# SeniorProjectBoard5.net
KiCad netlist of a schematic drawn in EAGLE
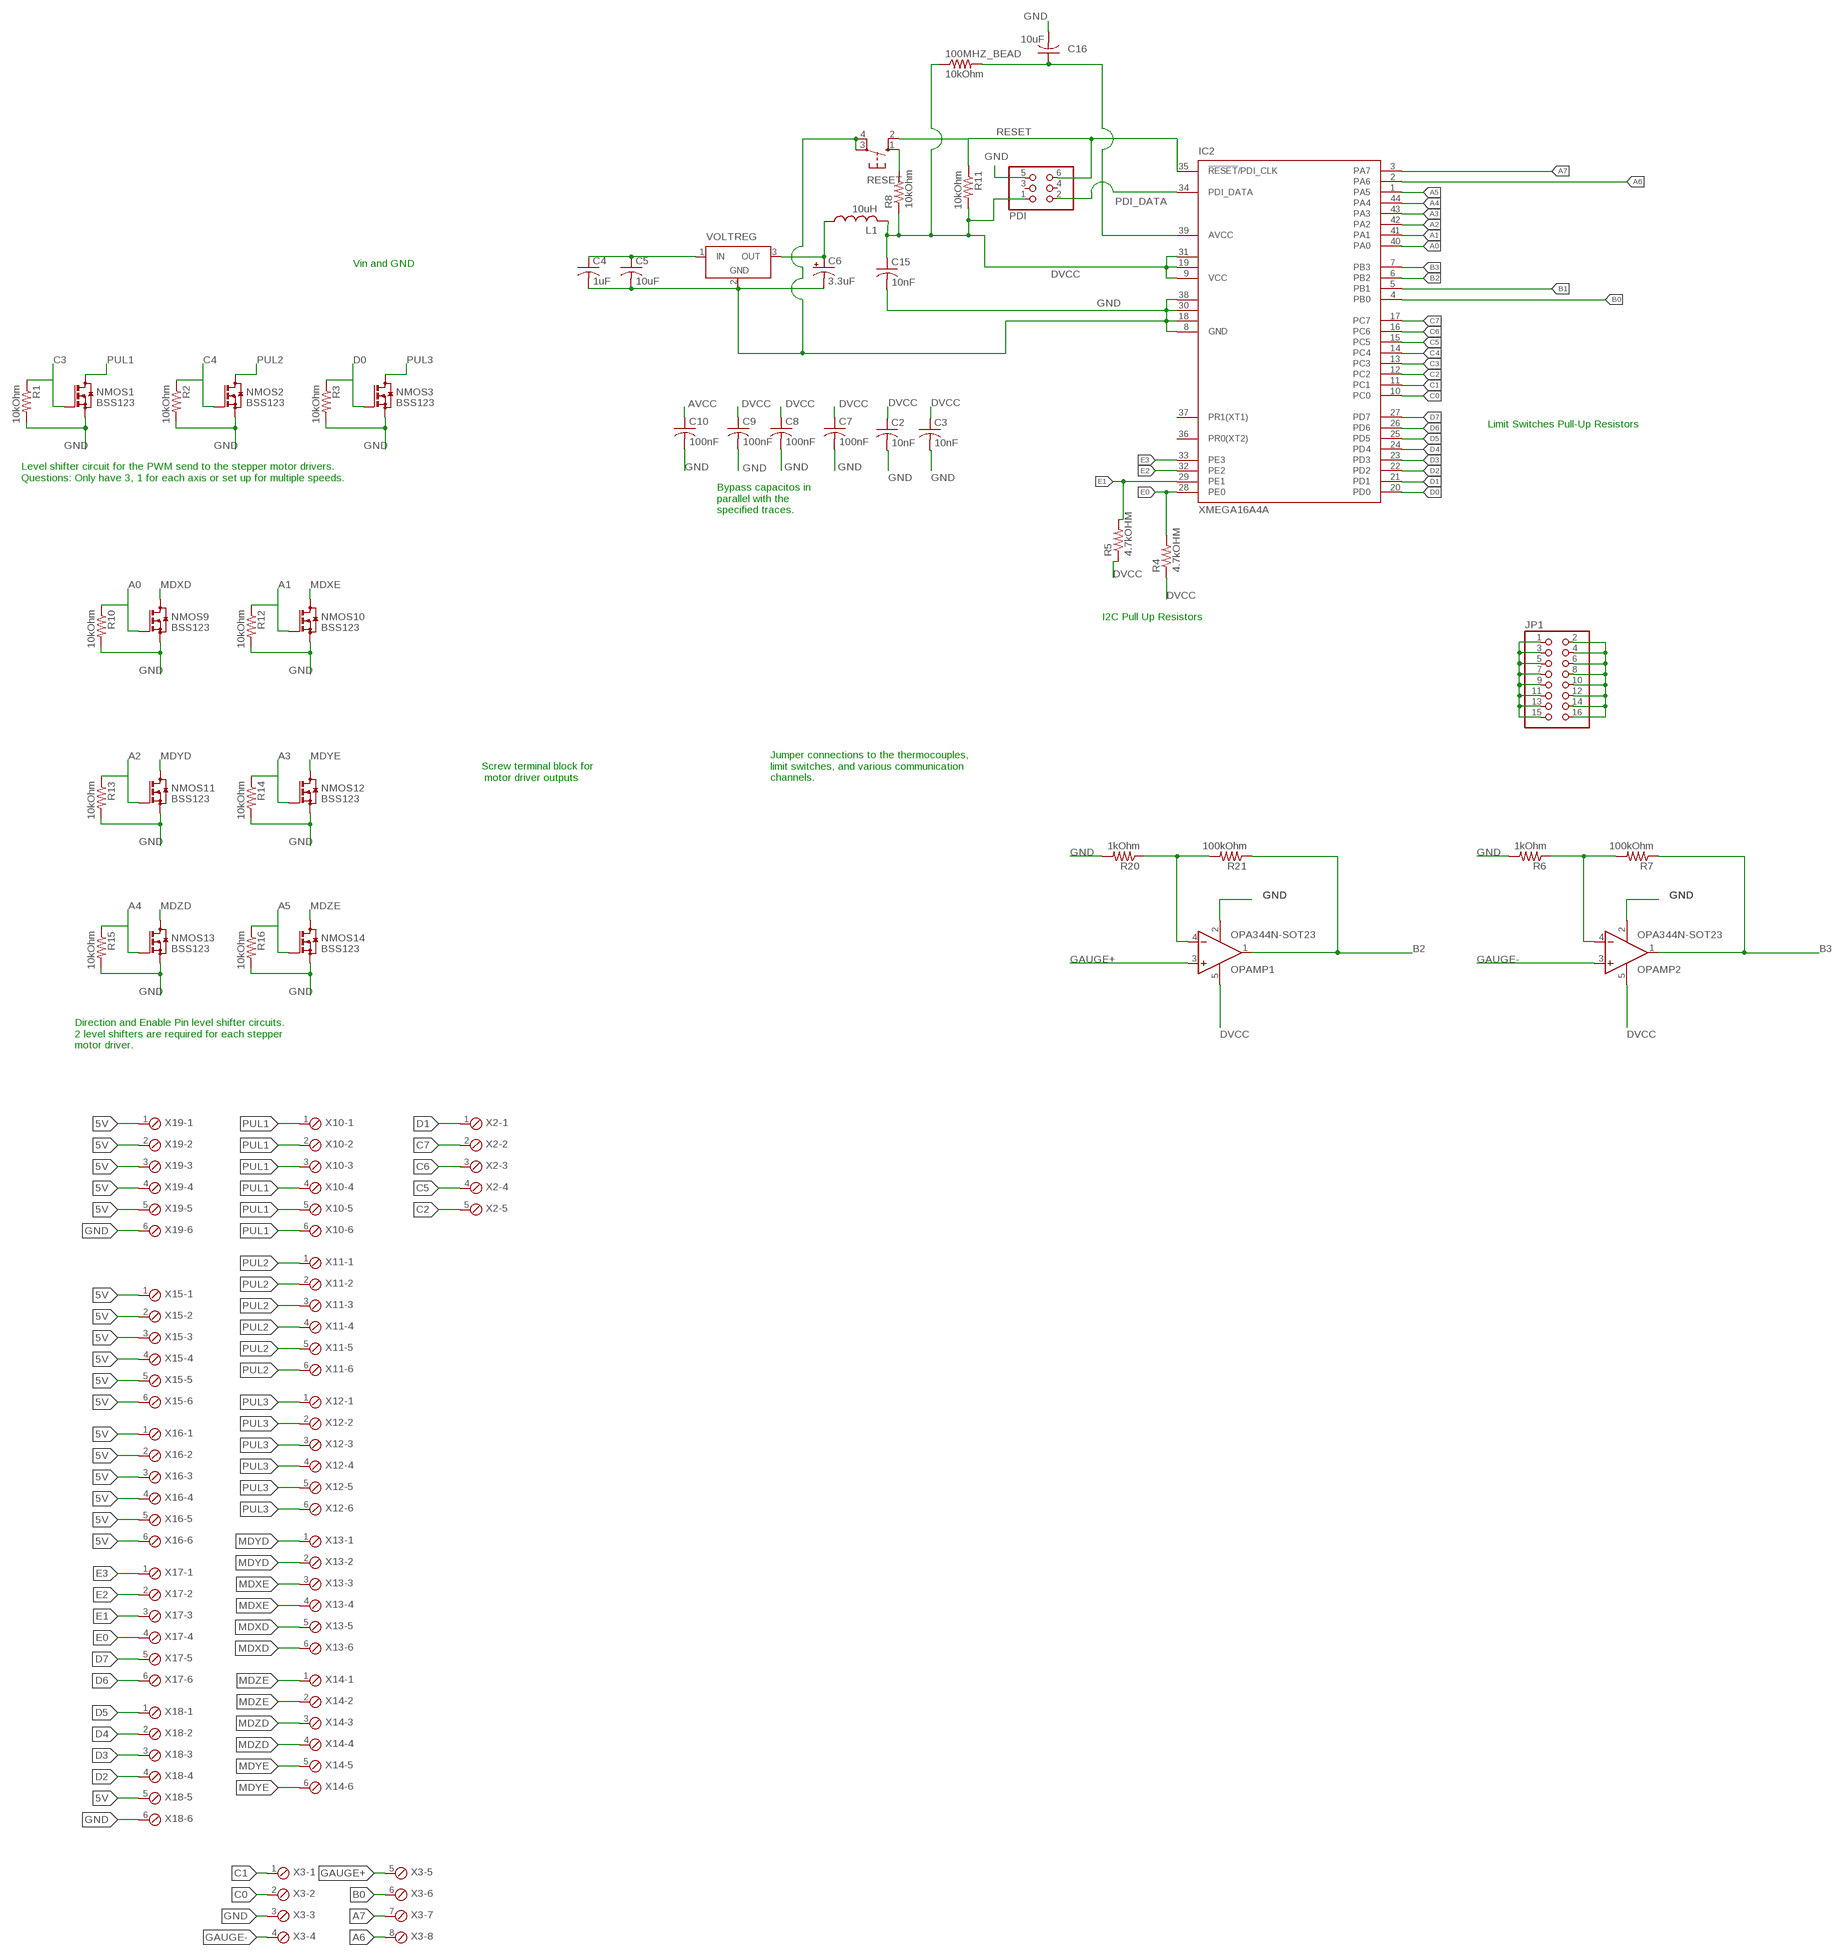
[diagram p0: schematic, sheet 1]

(export (version "E")
  (design (tool "Eeschema 10.0.6"))
  (components
    (comp (ref "100MHZ_BEAD")
      (value "10kOhm")
      (footprint "eagle-import:R0805")
      (libsource (lib "eagle-import") (part "R-US_R0805"))
    )
    (comp (ref "C2")
      (value "10nF")
      (footprint "eagle-import:C0805")
      (libsource (lib "eagle-import") (part "C-USC0805"))
    )
    (comp (ref "C3")
      (value "10nF")
      (footprint "eagle-import:C0805")
      (libsource (lib "eagle-import") (part "C-USC0805"))
    )
    (comp (ref "C4")
      (value "1uF")
      (footprint "eagle-import:C0805")
      (libsource (lib "eagle-import") (part "C-USC0805"))
    )
    (comp (ref "C5")
      (value "10uF")
      (footprint "eagle-import:C0805")
      (libsource (lib "eagle-import") (part "C-USC0805"))
    )
    (comp (ref "C6")
      (value "3.3uF")
      (footprint "eagle-import:CT3216")
      (libsource (lib "eagle-import") (part "CPOL-USCT3216"))
    )
    (comp (ref "C7")
      (value "100nF")
      (footprint "eagle-import:C0805")
      (libsource (lib "eagle-import") (part "C-USC0805"))
    )
    (comp (ref "C8")
      (value "100nF")
      (footprint "eagle-import:C0805")
      (libsource (lib "eagle-import") (part "C-USC0805"))
    )
    (comp (ref "C9")
      (value "100nF")
      (footprint "eagle-import:C0805")
      (libsource (lib "eagle-import") (part "C-USC0805"))
    )
    (comp (ref "C10")
      (value "100nF")
      (footprint "eagle-import:C0805")
      (libsource (lib "eagle-import") (part "C-USC0805"))
    )
    (comp (ref "C15")
      (value "10nF")
      (footprint "eagle-import:C0805")
      (libsource (lib "eagle-import") (part "C-USC0805"))
    )
    (comp (ref "C16")
      (value "10uF")
      (footprint "eagle-import:C0805")
      (libsource (lib "eagle-import") (part "C-USC0805"))
    )
    (comp (ref "IC2")
      (value "XMEGA16A4A")
      (footprint "eagle-import:TQFP44")
      (libsource (lib "eagle-import") (part "XMEGA16A4A"))
    )
    (comp (ref "JP1")
      (value "PINHD-2X8")
      (footprint "eagle-import:2X08")
      (libsource (lib "eagle-import") (part "PINHD-2X8"))
    )
    (comp (ref "L1")
      (value "10uH")
      (footprint "eagle-import:L1812")
      (libsource (lib "eagle-import") (part "L-USL1812"))
    )
    (comp (ref "NMOS1")
      (value "BSS123")
      (footprint "eagle-import:SOT23")
      (libsource (lib "eagle-import") (part "BSS123"))
    )
    (comp (ref "NMOS2")
      (value "BSS123")
      (footprint "eagle-import:SOT23")
      (libsource (lib "eagle-import") (part "BSS123"))
    )
    (comp (ref "NMOS3")
      (value "BSS123")
      (footprint "eagle-import:SOT23")
      (libsource (lib "eagle-import") (part "BSS123"))
    )
    (comp (ref "NMOS9")
      (value "BSS123")
      (footprint "eagle-import:SOT23")
      (libsource (lib "eagle-import") (part "BSS123"))
    )
    (comp (ref "NMOS10")
      (value "BSS123")
      (footprint "eagle-import:SOT23")
      (libsource (lib "eagle-import") (part "BSS123"))
    )
    (comp (ref "NMOS11")
      (value "BSS123")
      (footprint "eagle-import:SOT23")
      (libsource (lib "eagle-import") (part "BSS123"))
    )
    (comp (ref "NMOS12")
      (value "BSS123")
      (footprint "eagle-import:SOT23")
      (libsource (lib "eagle-import") (part "BSS123"))
    )
    (comp (ref "NMOS13")
      (value "BSS123")
      (footprint "eagle-import:SOT23")
      (libsource (lib "eagle-import") (part "BSS123"))
    )
    (comp (ref "NMOS14")
      (value "BSS123")
      (footprint "eagle-import:SOT23")
      (libsource (lib "eagle-import") (part "BSS123"))
    )
    (comp (ref "OPAMP1")
      (value "OPA344N-SOT23")
      (footprint "eagle-import:SOT23-5")
      (libsource (lib "eagle-import") (part "OPA-SOT23344N"))
    )
    (comp (ref "OPAMP2")
      (value "OPA344N-SOT23")
      (footprint "eagle-import:SOT23-5")
      (libsource (lib "eagle-import") (part "OPA-SOT23344N"))
    )
    (comp (ref "PDI")
      (value "PINHD-2X3")
      (footprint "eagle-import:2X03")
      (libsource (lib "eagle-import") (part "PINHD-2X3"))
    )
    (comp (ref "R1")
      (value "10kOhm")
      (footprint "eagle-import:R0805")
      (libsource (lib "eagle-import") (part "R-US_R0805"))
    )
    (comp (ref "R2")
      (value "10kOhm")
      (footprint "eagle-import:R0805")
      (libsource (lib "eagle-import") (part "R-US_R0805"))
    )
    (comp (ref "R3")
      (value "10kOhm")
      (footprint "eagle-import:R0805")
      (libsource (lib "eagle-import") (part "R-US_R0805"))
    )
    (comp (ref "R4")
      (value "4.7kOHM")
      (footprint "eagle-import:R0805")
      (libsource (lib "eagle-import") (part "R-US_R0805"))
    )
    (comp (ref "R5")
      (value "4.7kOHM")
      (footprint "eagle-import:R0805")
      (libsource (lib "eagle-import") (part "R-US_R0805"))
    )
    (comp (ref "R6")
      (value "1kOhm")
      (footprint "eagle-import:R0805")
      (libsource (lib "eagle-import") (part "R-US_R0805"))
    )
    (comp (ref "R7")
      (value "100kOhm")
      (footprint "eagle-import:R0805")
      (libsource (lib "eagle-import") (part "R-US_R0805"))
    )
    (comp (ref "R8")
      (value "10kOhm")
      (footprint "eagle-import:R0805")
      (libsource (lib "eagle-import") (part "R-US_R0805"))
    )
    (comp (ref "R10")
      (value "10kOhm")
      (footprint "eagle-import:R0805")
      (libsource (lib "eagle-import") (part "R-US_R0805"))
    )
    (comp (ref "R11")
      (value "10kOhm")
      (footprint "eagle-import:R0805")
      (libsource (lib "eagle-import") (part "R-US_R0805"))
    )
    (comp (ref "R12")
      (value "10kOhm")
      (footprint "eagle-import:R0805")
      (libsource (lib "eagle-import") (part "R-US_R0805"))
    )
    (comp (ref "R13")
      (value "10kOhm")
      (footprint "eagle-import:R0805")
      (libsource (lib "eagle-import") (part "R-US_R0805"))
    )
    (comp (ref "R14")
      (value "10kOhm")
      (footprint "eagle-import:R0805")
      (libsource (lib "eagle-import") (part "R-US_R0805"))
    )
    (comp (ref "R15")
      (value "10kOhm")
      (footprint "eagle-import:R0805")
      (libsource (lib "eagle-import") (part "R-US_R0805"))
    )
    (comp (ref "R16")
      (value "10kOhm")
      (footprint "eagle-import:R0805")
      (libsource (lib "eagle-import") (part "R-US_R0805"))
    )
    (comp (ref "R20")
      (value "1kOhm")
      (footprint "eagle-import:R0805")
      (libsource (lib "eagle-import") (part "R-US_R0805"))
    )
    (comp (ref "R21")
      (value "100kOhm")
      (footprint "eagle-import:R0805")
      (libsource (lib "eagle-import") (part "R-US_R0805"))
    )
    (comp (ref "RESET")
      (value "10-XX")
      (footprint "eagle-import:B3F-10XX")
      (fields (field (name "MPN") "B3F-1000"))
      (libsource (lib "eagle-import") (part "10-XX"))
    )
    (comp (ref "VOLTREG")
      (value "LT1129CST5")
      (footprint "eagle-import:SOT223")
      (fields (field (name "MPN") "LT1129CST-5#PBF"))
      (libsource (lib "eagle-import") (part "LT1129CST5"))
    )
    (comp (ref "X2")
      (value "MPT5")
      (footprint "eagle-import:5POL254")
      (libsource (lib "eagle-import") (part "MPT5"))
    )
    (comp (ref "X3")
      (value "MPT8")
      (footprint "eagle-import:8POL254")
      (libsource (lib "eagle-import") (part "MPT8"))
    )
    (comp (ref "X10")
      (value "MPT6")
      (footprint "eagle-import:6POL254")
      (libsource (lib "eagle-import") (part "MPT6"))
    )
    (comp (ref "X11")
      (value "MPT6")
      (footprint "eagle-import:6POL254")
      (libsource (lib "eagle-import") (part "MPT6"))
    )
    (comp (ref "X12")
      (value "MPT6")
      (footprint "eagle-import:6POL254")
      (libsource (lib "eagle-import") (part "MPT6"))
    )
    (comp (ref "X13")
      (value "MPT6")
      (footprint "eagle-import:6POL254")
      (libsource (lib "eagle-import") (part "MPT6"))
    )
    (comp (ref "X14")
      (value "MPT6")
      (footprint "eagle-import:6POL254")
      (libsource (lib "eagle-import") (part "MPT6"))
    )
    (comp (ref "X15")
      (value "MPT6")
      (footprint "eagle-import:6POL254")
      (libsource (lib "eagle-import") (part "MPT6"))
    )
    (comp (ref "X16")
      (value "MPT6")
      (footprint "eagle-import:6POL254")
      (libsource (lib "eagle-import") (part "MPT6"))
    )
    (comp (ref "X17")
      (value "MPT6")
      (footprint "eagle-import:6POL254")
      (libsource (lib "eagle-import") (part "MPT6"))
    )
    (comp (ref "X18")
      (value "MPT6")
      (footprint "eagle-import:6POL254")
      (libsource (lib "eagle-import") (part "MPT6"))
    )
    (comp (ref "X19")
      (value "MPT6")
      (footprint "eagle-import:6POL254")
      (libsource (lib "eagle-import") (part "MPT6"))
    )
  )
  (nets
    (net (code "1") (name "/AVCC") (class "Default")
      (node (ref "100MHZ_BEAD") (pin "2") (pinfunction "2_2") (pintype "passive"))
      (node (ref "C10") (pin "1") (pinfunction "1_1") (pintype "passive"))
      (node (ref "C16") (pin "1") (pinfunction "1_1") (pintype "passive"))
      (node (ref "IC2") (pin "39") (pinfunction "AVCC_39") (pintype "power_in"))
    )
    (net (code "2") (name "/DVCC") (class "Default")
      (node (ref "100MHZ_BEAD") (pin "1") (pinfunction "1_1") (pintype "passive"))
      (node (ref "C15") (pin "1") (pinfunction "1_1") (pintype "passive"))
      (node (ref "C2") (pin "1") (pinfunction "1_1") (pintype "passive"))
      (node (ref "C3") (pin "1") (pinfunction "1_1") (pintype "passive"))
      (node (ref "C7") (pin "1") (pinfunction "1_1") (pintype "passive"))
      (node (ref "C8") (pin "1") (pinfunction "1_1") (pintype "passive"))
      (node (ref "C9") (pin "1") (pinfunction "1_1") (pintype "passive"))
      (node (ref "IC2") (pin "19") (pinfunction "VCC1_19") (pintype "power_in"))
      (node (ref "IC2") (pin "31") (pinfunction "VCC2_31") (pintype "power_in"))
      (node (ref "IC2") (pin "9") (pinfunction "VCC_9") (pintype "power_in"))
      (node (ref "JP1") (pin "1") (pinfunction "1_1") (pintype "passive"))
      (node (ref "JP1") (pin "11") (pinfunction "11_11") (pintype "passive"))
      (node (ref "JP1") (pin "13") (pinfunction "13_13") (pintype "passive"))
      (node (ref "JP1") (pin "15") (pinfunction "15_15") (pintype "passive"))
      (node (ref "JP1") (pin "3") (pinfunction "3_3") (pintype "passive"))
      (node (ref "JP1") (pin "5") (pinfunction "5_5") (pintype "passive"))
      (node (ref "JP1") (pin "7") (pinfunction "7_7") (pintype "passive"))
      (node (ref "JP1") (pin "9") (pinfunction "9_9") (pintype "passive"))
      (node (ref "L1") (pin "2") (pinfunction "2_2") (pintype "passive"))
      (node (ref "OPAMP1") (pin "5") (pinfunction "V+_5") (pintype "power_in"))
      (node (ref "OPAMP2") (pin "5") (pinfunction "V+_5") (pintype "power_in"))
      (node (ref "PDI") (pin "1") (pinfunction "1_1") (pintype "passive"))
      (node (ref "R11") (pin "2") (pinfunction "2_2") (pintype "passive"))
      (node (ref "R4") (pin "1") (pinfunction "1_1") (pintype "passive"))
      (node (ref "R5") (pin "1") (pinfunction "1_1") (pintype "passive"))
      (node (ref "R8") (pin "1") (pinfunction "1_1") (pintype "passive"))
    )
    (net (code "3") (name "/PDI_DATA") (class "Default")
      (node (ref "IC2") (pin "34") (pinfunction "PDI_DATA_34") (pintype "bidirectional"))
      (node (ref "PDI") (pin "2") (pinfunction "2_2") (pintype "passive"))
    )
    (net (code "4") (name "/RESET") (class "Default")
      (node (ref "IC2") (pin "35") (pinfunction "~{RESET}/PDI_CLK_35") (pintype "bidirectional"))
      (node (ref "PDI") (pin "6") (pinfunction "6_6") (pintype "passive"))
      (node (ref "R11") (pin "1") (pinfunction "1_1") (pintype "passive"))
      (node (ref "RESET") (pin "2") (pinfunction "S1_2") (pintype "passive"))
    )
    (net (code "5") (name "5V") (class "Default")
      (node (ref "C4") (pin "1") (pinfunction "1_1") (pintype "passive"))
      (node (ref "C5") (pin "1") (pinfunction "1_1") (pintype "passive"))
      (node (ref "VOLTREG") (pin "1") (pinfunction "IN_1") (pintype "input"))
      (node (ref "X15") (pin "1") (pinfunction "1_1") (pintype "passive"))
      (node (ref "X15") (pin "2") (pinfunction "1_2") (pintype "passive"))
      (node (ref "X15") (pin "3") (pinfunction "1_3") (pintype "passive"))
      (node (ref "X15") (pin "4") (pinfunction "1_4") (pintype "passive"))
      (node (ref "X15") (pin "5") (pinfunction "1_5") (pintype "passive"))
      (node (ref "X15") (pin "6") (pinfunction "1_6") (pintype "passive"))
      (node (ref "X16") (pin "1") (pinfunction "1_1") (pintype "passive"))
      (node (ref "X16") (pin "2") (pinfunction "1_2") (pintype "passive"))
      (node (ref "X16") (pin "3") (pinfunction "1_3") (pintype "passive"))
      (node (ref "X16") (pin "4") (pinfunction "1_4") (pintype "passive"))
      (node (ref "X16") (pin "5") (pinfunction "1_5") (pintype "passive"))
      (node (ref "X16") (pin "6") (pinfunction "1_6") (pintype "passive"))
      (node (ref "X18") (pin "5") (pinfunction "1_5") (pintype "passive"))
      (node (ref "X19") (pin "1") (pinfunction "1_1") (pintype "passive"))
      (node (ref "X19") (pin "2") (pinfunction "1_2") (pintype "passive"))
      (node (ref "X19") (pin "3") (pinfunction "1_3") (pintype "passive"))
      (node (ref "X19") (pin "4") (pinfunction "1_4") (pintype "passive"))
      (node (ref "X19") (pin "5") (pinfunction "1_5") (pintype "passive"))
    )
    (net (code "6") (name "A0") (class "Default")
      (node (ref "IC2") (pin "40") (pinfunction "PA0_40") (pintype "bidirectional"))
      (node (ref "NMOS9") (pin "1") (pinfunction "G_1") (pintype "passive"))
      (node (ref "R10") (pin "1") (pinfunction "1_1") (pintype "passive"))
    )
    (net (code "7") (name "A1") (class "Default")
      (node (ref "IC2") (pin "41") (pinfunction "PA1_41") (pintype "bidirectional"))
      (node (ref "NMOS10") (pin "1") (pinfunction "G_1") (pintype "passive"))
      (node (ref "R12") (pin "1") (pinfunction "1_1") (pintype "passive"))
    )
    (net (code "8") (name "A2") (class "Default")
      (node (ref "IC2") (pin "42") (pinfunction "PA2_42") (pintype "bidirectional"))
      (node (ref "NMOS11") (pin "1") (pinfunction "G_1") (pintype "passive"))
      (node (ref "R13") (pin "1") (pinfunction "1_1") (pintype "passive"))
    )
    (net (code "9") (name "A3") (class "Default")
      (node (ref "IC2") (pin "43") (pinfunction "PA3_43") (pintype "bidirectional"))
      (node (ref "NMOS12") (pin "1") (pinfunction "G_1") (pintype "passive"))
      (node (ref "R14") (pin "1") (pinfunction "1_1") (pintype "passive"))
    )
    (net (code "10") (name "A4") (class "Default")
      (node (ref "IC2") (pin "44") (pinfunction "PA4_44") (pintype "bidirectional"))
      (node (ref "NMOS13") (pin "1") (pinfunction "G_1") (pintype "passive"))
      (node (ref "R15") (pin "1") (pinfunction "1_1") (pintype "passive"))
    )
    (net (code "11") (name "A5") (class "Default")
      (node (ref "IC2") (pin "1") (pinfunction "PA5_1") (pintype "bidirectional"))
      (node (ref "NMOS14") (pin "1") (pinfunction "G_1") (pintype "passive"))
      (node (ref "R16") (pin "1") (pinfunction "1_1") (pintype "passive"))
    )
    (net (code "12") (name "A6") (class "Default")
      (node (ref "IC2") (pin "2") (pinfunction "PA6_2") (pintype "bidirectional"))
      (node (ref "X3") (pin "8") (pinfunction "1_8") (pintype "passive"))
    )
    (net (code "13") (name "A7") (class "Default")
      (node (ref "IC2") (pin "3") (pinfunction "PA7_3") (pintype "bidirectional"))
      (node (ref "X3") (pin "7") (pinfunction "1_7") (pintype "passive"))
    )
    (net (code "14") (name "B0") (class "Default")
      (node (ref "IC2") (pin "4") (pinfunction "PB0_4") (pintype "bidirectional"))
      (node (ref "X3") (pin "6") (pinfunction "1_6") (pintype "passive"))
    )
    (net (code "15") (name "B1") (class "Default")
      (node (ref "IC2") (pin "5") (pinfunction "PB1_5") (pintype "bidirectional"))
    )
    (net (code "16") (name "B2") (class "Default")
      (node (ref "IC2") (pin "6") (pinfunction "PB2_6") (pintype "bidirectional"))
      (node (ref "OPAMP1") (pin "1") (pinfunction "OUT_1") (pintype "output"))
      (node (ref "R21") (pin "1") (pinfunction "1_1") (pintype "passive"))
    )
    (net (code "17") (name "B3") (class "Default")
      (node (ref "IC2") (pin "7") (pinfunction "PB3_7") (pintype "bidirectional"))
      (node (ref "OPAMP2") (pin "1") (pinfunction "OUT_1") (pintype "output"))
      (node (ref "R7") (pin "1") (pinfunction "1_1") (pintype "passive"))
    )
    (net (code "18") (name "C0") (class "Default")
      (node (ref "IC2") (pin "10") (pinfunction "PC0_10") (pintype "bidirectional"))
      (node (ref "X3") (pin "2") (pinfunction "1_2") (pintype "passive"))
    )
    (net (code "19") (name "C1") (class "Default")
      (node (ref "IC2") (pin "11") (pinfunction "PC1_11") (pintype "bidirectional"))
      (node (ref "X3") (pin "1") (pinfunction "1_1") (pintype "passive"))
    )
    (net (code "20") (name "C2") (class "Default")
      (node (ref "IC2") (pin "12") (pinfunction "PC2_12") (pintype "bidirectional"))
      (node (ref "X2") (pin "5") (pinfunction "1_5") (pintype "passive"))
    )
    (net (code "21") (name "C3") (class "Default")
      (node (ref "IC2") (pin "13") (pinfunction "PC3_13") (pintype "bidirectional"))
      (node (ref "NMOS1") (pin "1") (pinfunction "G_1") (pintype "passive"))
      (node (ref "R1") (pin "1") (pinfunction "1_1") (pintype "passive"))
    )
    (net (code "22") (name "C4") (class "Default")
      (node (ref "IC2") (pin "14") (pinfunction "PC4_14") (pintype "bidirectional"))
      (node (ref "NMOS2") (pin "1") (pinfunction "G_1") (pintype "passive"))
      (node (ref "R2") (pin "1") (pinfunction "1_1") (pintype "passive"))
    )
    (net (code "23") (name "C5") (class "Default")
      (node (ref "IC2") (pin "15") (pinfunction "PC5_15") (pintype "bidirectional"))
      (node (ref "X2") (pin "4") (pinfunction "1_4") (pintype "passive"))
    )
    (net (code "24") (name "C6") (class "Default")
      (node (ref "IC2") (pin "16") (pinfunction "PC6_16") (pintype "bidirectional"))
      (node (ref "X2") (pin "3") (pinfunction "1_3") (pintype "passive"))
    )
    (net (code "25") (name "C7") (class "Default")
      (node (ref "IC2") (pin "17") (pinfunction "PC7_17") (pintype "bidirectional"))
      (node (ref "X2") (pin "2") (pinfunction "1_2") (pintype "passive"))
    )
    (net (code "26") (name "D0") (class "Default")
      (node (ref "IC2") (pin "20") (pinfunction "PD0_20") (pintype "bidirectional"))
      (node (ref "NMOS3") (pin "1") (pinfunction "G_1") (pintype "passive"))
      (node (ref "R3") (pin "1") (pinfunction "1_1") (pintype "passive"))
    )
    (net (code "27") (name "D1") (class "Default")
      (node (ref "IC2") (pin "21") (pinfunction "PD1_21") (pintype "bidirectional"))
      (node (ref "X2") (pin "1") (pinfunction "1_1") (pintype "passive"))
    )
    (net (code "28") (name "D2") (class "Default")
      (node (ref "IC2") (pin "22") (pinfunction "PD2_22") (pintype "bidirectional"))
      (node (ref "X18") (pin "4") (pinfunction "1_4") (pintype "passive"))
    )
    (net (code "29") (name "D3") (class "Default")
      (node (ref "IC2") (pin "23") (pinfunction "PD3_23") (pintype "bidirectional"))
      (node (ref "X18") (pin "3") (pinfunction "1_3") (pintype "passive"))
    )
    (net (code "30") (name "D4") (class "Default")
      (node (ref "IC2") (pin "24") (pinfunction "PD4_24") (pintype "bidirectional"))
      (node (ref "X18") (pin "2") (pinfunction "1_2") (pintype "passive"))
    )
    (net (code "31") (name "D5") (class "Default")
      (node (ref "IC2") (pin "25") (pinfunction "PD5_25") (pintype "bidirectional"))
      (node (ref "X18") (pin "1") (pinfunction "1_1") (pintype "passive"))
    )
    (net (code "32") (name "D6") (class "Default")
      (node (ref "IC2") (pin "26") (pinfunction "PD6_26") (pintype "bidirectional"))
      (node (ref "X17") (pin "6") (pinfunction "1_6") (pintype "passive"))
    )
    (net (code "33") (name "D7") (class "Default")
      (node (ref "IC2") (pin "27") (pinfunction "PD7_27") (pintype "bidirectional"))
      (node (ref "X17") (pin "5") (pinfunction "1_5") (pintype "passive"))
    )
    (net (code "34") (name "E0") (class "Default")
      (node (ref "IC2") (pin "28") (pinfunction "PE0_28") (pintype "bidirectional"))
      (node (ref "R4") (pin "2") (pinfunction "2_2") (pintype "passive"))
      (node (ref "X17") (pin "4") (pinfunction "1_4") (pintype "passive"))
    )
    (net (code "35") (name "E1") (class "Default")
      (node (ref "IC2") (pin "29") (pinfunction "PE1_29") (pintype "bidirectional"))
      (node (ref "R5") (pin "2") (pinfunction "2_2") (pintype "passive"))
      (node (ref "X17") (pin "3") (pinfunction "1_3") (pintype "passive"))
    )
    (net (code "36") (name "E2") (class "Default")
      (node (ref "IC2") (pin "32") (pinfunction "PE2_32") (pintype "bidirectional"))
      (node (ref "X17") (pin "2") (pinfunction "1_2") (pintype "passive"))
    )
    (net (code "37") (name "E3") (class "Default")
      (node (ref "IC2") (pin "33") (pinfunction "PE3_33") (pintype "bidirectional"))
      (node (ref "X17") (pin "1") (pinfunction "1_1") (pintype "passive"))
    )
    (net (code "38") (name "GAUGE+") (class "Default")
      (node (ref "OPAMP1") (pin "3") (pinfunction "+IN_3") (pintype "input"))
      (node (ref "X3") (pin "5") (pinfunction "1_5") (pintype "passive"))
    )
    (net (code "39") (name "GAUGE-") (class "Default")
      (node (ref "OPAMP2") (pin "3") (pinfunction "+IN_3") (pintype "input"))
      (node (ref "X3") (pin "4") (pinfunction "1_4") (pintype "passive"))
    )
    (net (code "40") (name "GND") (class "Default")
      (node (ref "C10") (pin "2") (pinfunction "2_2") (pintype "passive"))
      (node (ref "C15") (pin "2") (pinfunction "2_2") (pintype "passive"))
      (node (ref "C16") (pin "2") (pinfunction "2_2") (pintype "passive"))
      (node (ref "C2") (pin "2") (pinfunction "2_2") (pintype "passive"))
      (node (ref "C3") (pin "2") (pinfunction "2_2") (pintype "passive"))
      (node (ref "C4") (pin "2") (pinfunction "2_2") (pintype "passive"))
      (node (ref "C5") (pin "2") (pinfunction "2_2") (pintype "passive"))
      (node (ref "C6") (pin "-") (pinfunction "-_-") (pintype "passive"))
      (node (ref "C7") (pin "2") (pinfunction "2_2") (pintype "passive"))
      (node (ref "C8") (pin "2") (pinfunction "2_2") (pintype "passive"))
      (node (ref "C9") (pin "2") (pinfunction "2_2") (pintype "passive"))
      (node (ref "IC2") (pin "18") (pinfunction "GND1_18") (pintype "power_in"))
      (node (ref "IC2") (pin "30") (pinfunction "GND2_30") (pintype "power_in"))
      (node (ref "IC2") (pin "38") (pinfunction "GND3_38") (pintype "power_in"))
      (node (ref "IC2") (pin "8") (pinfunction "GND_8") (pintype "power_in"))
      (node (ref "JP1") (pin "10") (pinfunction "10_10") (pintype "passive"))
      (node (ref "JP1") (pin "12") (pinfunction "12_12") (pintype "passive"))
      (node (ref "JP1") (pin "14") (pinfunction "14_14") (pintype "passive"))
      (node (ref "JP1") (pin "16") (pinfunction "16_16") (pintype "passive"))
      (node (ref "JP1") (pin "2") (pinfunction "2_2") (pintype "passive"))
      (node (ref "JP1") (pin "4") (pinfunction "4_4") (pintype "passive"))
      (node (ref "JP1") (pin "6") (pinfunction "6_6") (pintype "passive"))
      (node (ref "JP1") (pin "8") (pinfunction "8_8") (pintype "passive"))
      (node (ref "NMOS1") (pin "2") (pinfunction "S_2") (pintype "passive"))
      (node (ref "NMOS10") (pin "2") (pinfunction "S_2") (pintype "passive"))
      (node (ref "NMOS11") (pin "2") (pinfunction "S_2") (pintype "passive"))
      (node (ref "NMOS12") (pin "2") (pinfunction "S_2") (pintype "passive"))
      (node (ref "NMOS13") (pin "2") (pinfunction "S_2") (pintype "passive"))
      (node (ref "NMOS14") (pin "2") (pinfunction "S_2") (pintype "passive"))
      (node (ref "NMOS2") (pin "2") (pinfunction "S_2") (pintype "passive"))
      (node (ref "NMOS3") (pin "2") (pinfunction "S_2") (pintype "passive"))
      (node (ref "NMOS9") (pin "2") (pinfunction "S_2") (pintype "passive"))
      (node (ref "OPAMP1") (pin "2") (pinfunction "V-_2") (pintype "power_in"))
      (node (ref "OPAMP2") (pin "2") (pinfunction "V-_2") (pintype "power_in"))
      (node (ref "PDI") (pin "5") (pinfunction "5_5") (pintype "passive"))
      (node (ref "R1") (pin "2") (pinfunction "2_2") (pintype "passive"))
      (node (ref "R10") (pin "2") (pinfunction "2_2") (pintype "passive"))
      (node (ref "R12") (pin "2") (pinfunction "2_2") (pintype "passive"))
      (node (ref "R13") (pin "2") (pinfunction "2_2") (pintype "passive"))
      (node (ref "R14") (pin "2") (pinfunction "2_2") (pintype "passive"))
      (node (ref "R15") (pin "2") (pinfunction "2_2") (pintype "passive"))
      (node (ref "R16") (pin "2") (pinfunction "2_2") (pintype "passive"))
      (node (ref "R2") (pin "2") (pinfunction "2_2") (pintype "passive"))
      (node (ref "R20") (pin "2") (pinfunction "2_2") (pintype "passive"))
      (node (ref "R3") (pin "2") (pinfunction "2_2") (pintype "passive"))
      (node (ref "R6") (pin "2") (pinfunction "2_2") (pintype "passive"))
      (node (ref "RESET") (pin "3") (pinfunction "P_3") (pintype "passive"))
      (node (ref "RESET") (pin "4") (pinfunction "P1_4") (pintype "passive"))
      (node (ref "VOLTREG") (pin "2") (pinfunction "GND_2") (pintype "power_in"))
      (node (ref "X18") (pin "6") (pinfunction "1_6") (pintype "passive"))
      (node (ref "X19") (pin "6") (pinfunction "1_6") (pintype "passive"))
      (node (ref "X3") (pin "3") (pinfunction "1_3") (pintype "passive"))
    )
    (net (code "41") (name "MDXD") (class "Default")
      (node (ref "NMOS9") (pin "3") (pinfunction "D_3") (pintype "passive"))
      (node (ref "X13") (pin "5") (pinfunction "1_5") (pintype "passive"))
      (node (ref "X13") (pin "6") (pinfunction "1_6") (pintype "passive"))
    )
    (net (code "42") (name "MDXE") (class "Default")
      (node (ref "NMOS10") (pin "3") (pinfunction "D_3") (pintype "passive"))
      (node (ref "X13") (pin "3") (pinfunction "1_3") (pintype "passive"))
      (node (ref "X13") (pin "4") (pinfunction "1_4") (pintype "passive"))
    )
    (net (code "43") (name "MDYD") (class "Default")
      (node (ref "NMOS11") (pin "3") (pinfunction "D_3") (pintype "passive"))
      (node (ref "X13") (pin "1") (pinfunction "1_1") (pintype "passive"))
      (node (ref "X13") (pin "2") (pinfunction "1_2") (pintype "passive"))
    )
    (net (code "44") (name "MDYE") (class "Default")
      (node (ref "NMOS12") (pin "3") (pinfunction "D_3") (pintype "passive"))
      (node (ref "X14") (pin "5") (pinfunction "1_5") (pintype "passive"))
      (node (ref "X14") (pin "6") (pinfunction "1_6") (pintype "passive"))
    )
    (net (code "45") (name "MDZD") (class "Default")
      (node (ref "NMOS13") (pin "3") (pinfunction "D_3") (pintype "passive"))
      (node (ref "X14") (pin "3") (pinfunction "1_3") (pintype "passive"))
      (node (ref "X14") (pin "4") (pinfunction "1_4") (pintype "passive"))
    )
    (net (code "46") (name "MDZE") (class "Default")
      (node (ref "NMOS14") (pin "3") (pinfunction "D_3") (pintype "passive"))
      (node (ref "X14") (pin "1") (pinfunction "1_1") (pintype "passive"))
      (node (ref "X14") (pin "2") (pinfunction "1_2") (pintype "passive"))
    )
    (net (code "47") (name "Net-(OPAMP1--IN)") (class "Default")
      (node (ref "OPAMP1") (pin "4") (pinfunction "-IN_4") (pintype "input"))
      (node (ref "R20") (pin "1") (pinfunction "1_1") (pintype "passive"))
      (node (ref "R21") (pin "2") (pinfunction "2_2") (pintype "passive"))
    )
    (net (code "48") (name "Net-(OPAMP2--IN)") (class "Default")
      (node (ref "OPAMP2") (pin "4") (pinfunction "-IN_4") (pintype "input"))
      (node (ref "R6") (pin "1") (pinfunction "1_1") (pintype "passive"))
      (node (ref "R7") (pin "2") (pinfunction "2_2") (pintype "passive"))
    )
    (net (code "49") (name "Net-(RESET-S)") (class "Default")
      (node (ref "R8") (pin "2") (pinfunction "2_2") (pintype "passive"))
      (node (ref "RESET") (pin "1") (pinfunction "S_1") (pintype "passive"))
    )
    (net (code "50") (name "Net-(VOLTREGA-OUT)") (class "Default")
      (node (ref "C6") (pin "+") (pinfunction "+_+") (pintype "passive"))
      (node (ref "L1") (pin "1") (pinfunction "1_1") (pintype "passive"))
      (node (ref "VOLTREG") (pin "3") (pinfunction "OUT_3") (pintype "output"))
    )
    (net (code "51") (name "PUL1") (class "Default")
      (node (ref "NMOS1") (pin "3") (pinfunction "D_3") (pintype "passive"))
      (node (ref "X10") (pin "1") (pinfunction "1_1") (pintype "passive"))
      (node (ref "X10") (pin "2") (pinfunction "1_2") (pintype "passive"))
      (node (ref "X10") (pin "3") (pinfunction "1_3") (pintype "passive"))
      (node (ref "X10") (pin "4") (pinfunction "1_4") (pintype "passive"))
      (node (ref "X10") (pin "5") (pinfunction "1_5") (pintype "passive"))
      (node (ref "X10") (pin "6") (pinfunction "1_6") (pintype "passive"))
    )
    (net (code "52") (name "PUL2") (class "Default")
      (node (ref "NMOS2") (pin "3") (pinfunction "D_3") (pintype "passive"))
      (node (ref "X11") (pin "1") (pinfunction "1_1") (pintype "passive"))
      (node (ref "X11") (pin "2") (pinfunction "1_2") (pintype "passive"))
      (node (ref "X11") (pin "3") (pinfunction "1_3") (pintype "passive"))
      (node (ref "X11") (pin "4") (pinfunction "1_4") (pintype "passive"))
      (node (ref "X11") (pin "5") (pinfunction "1_5") (pintype "passive"))
      (node (ref "X11") (pin "6") (pinfunction "1_6") (pintype "passive"))
    )
    (net (code "53") (name "PUL3") (class "Default")
      (node (ref "NMOS3") (pin "3") (pinfunction "D_3") (pintype "passive"))
      (node (ref "X12") (pin "1") (pinfunction "1_1") (pintype "passive"))
      (node (ref "X12") (pin "2") (pinfunction "1_2") (pintype "passive"))
      (node (ref "X12") (pin "3") (pinfunction "1_3") (pintype "passive"))
      (node (ref "X12") (pin "4") (pinfunction "1_4") (pintype "passive"))
      (node (ref "X12") (pin "5") (pinfunction "1_5") (pintype "passive"))
      (node (ref "X12") (pin "6") (pinfunction "1_6") (pintype "passive"))
    )
    (net (code "54") (name "unconnected-(IC2-PR0(XT2)-Pad36)") (class "Default")
      (node (ref "IC2") (pin "36") (pinfunction "PR0(XT2)_36") (pintype "bidirectional"))
    )
    (net (code "55") (name "unconnected-(IC2-PR1(XT1)-Pad37)") (class "Default")
      (node (ref "IC2") (pin "37") (pinfunction "PR1(XT1)_37") (pintype "bidirectional"))
    )
    (net (code "56") (name "unconnected-(PDI-Pad3)") (class "Default")
      (node (ref "PDI") (pin "3") (pinfunction "3_3") (pintype "passive"))
    )
    (net (code "57") (name "unconnected-(PDI-Pad4)") (class "Default")
      (node (ref "PDI") (pin "4") (pinfunction "4_4") (pintype "passive"))
    )
  )
)
